# ATmega328p-DHT11-DS1307-LCD.net
KiCad netlist of a schematic drawn in EAGLE
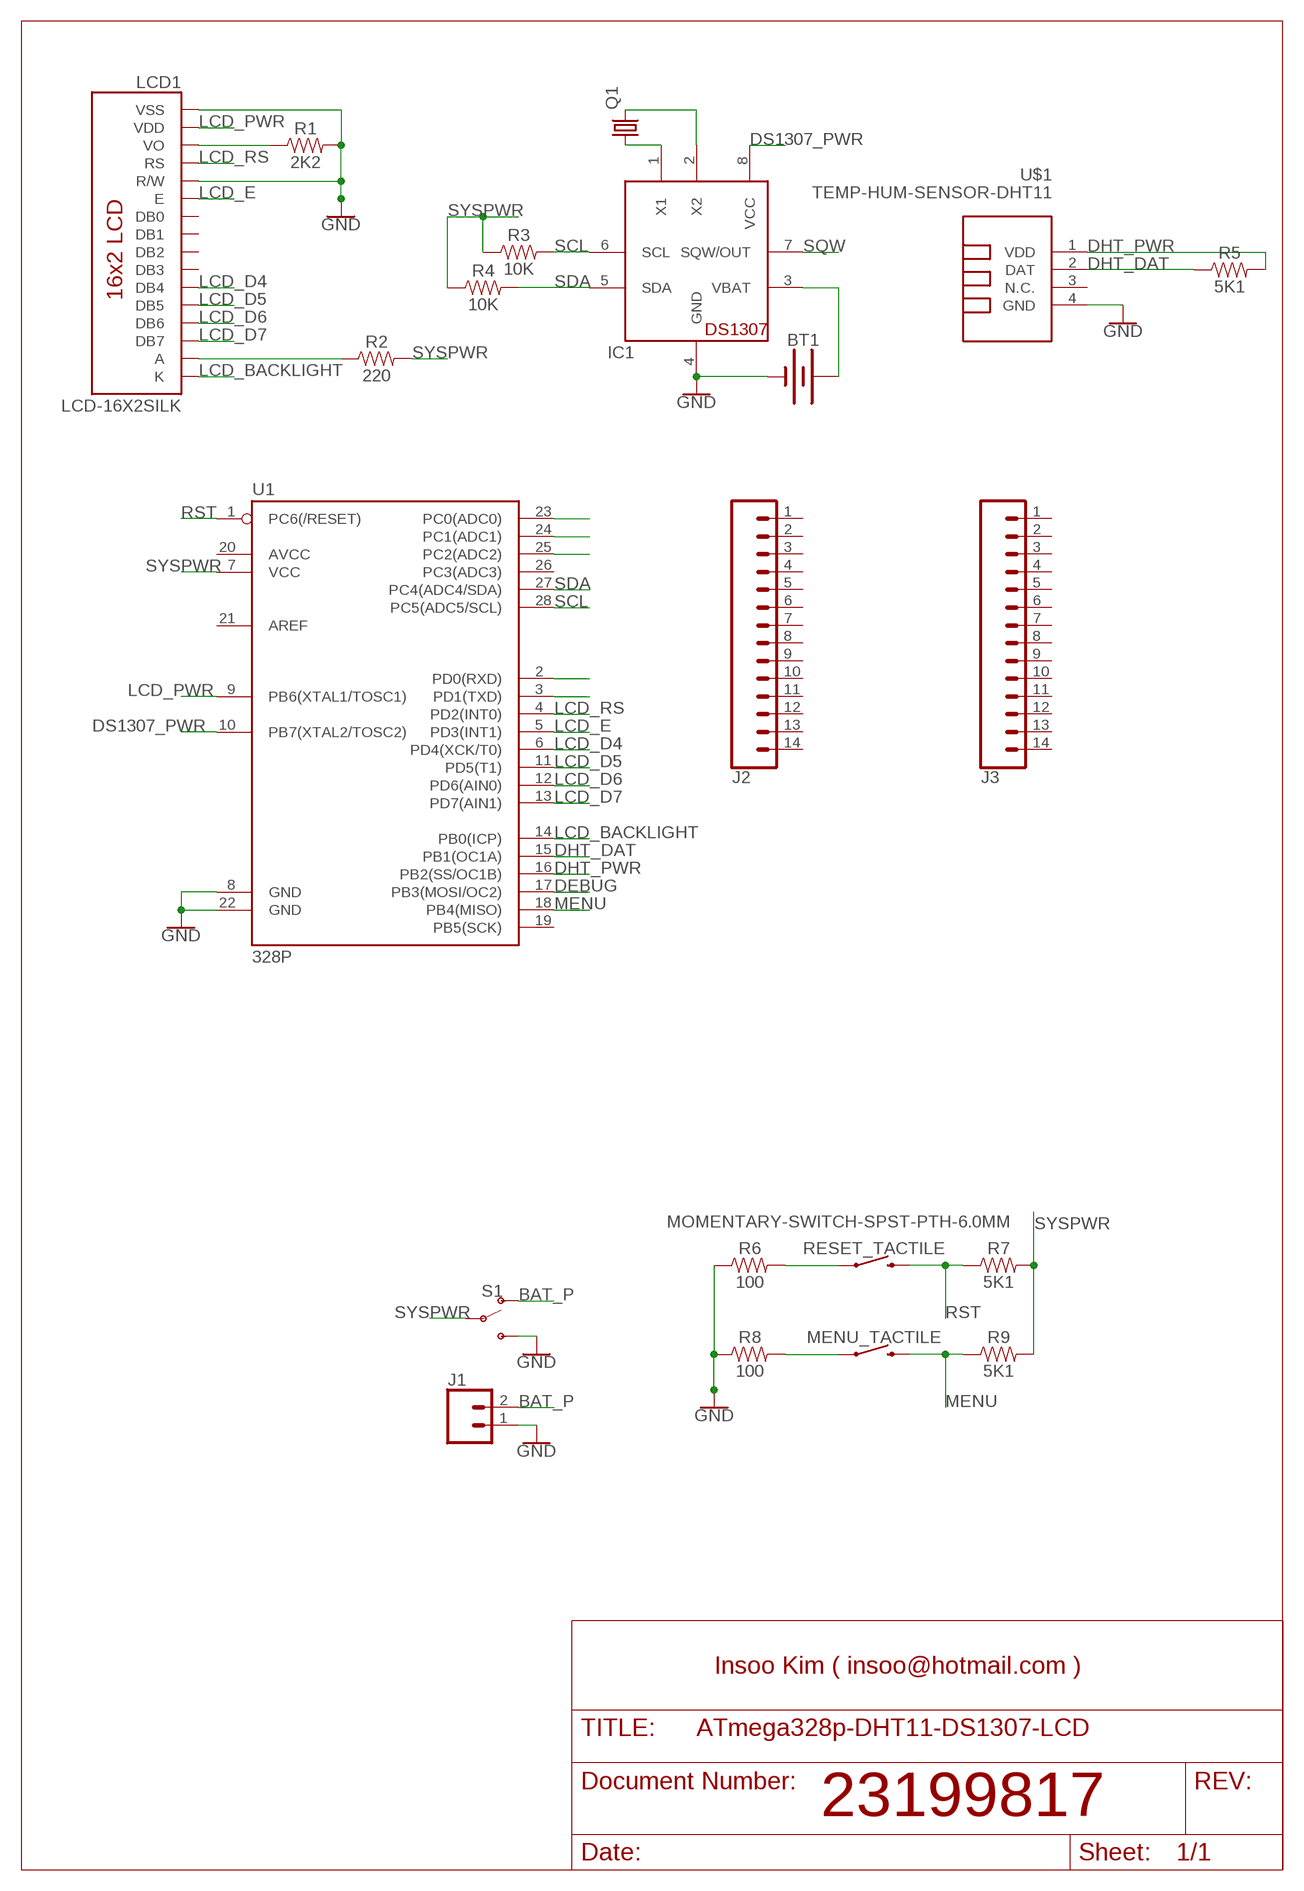
[diagram p0: schematic, sheet 1]

(export (version "E")
  (design (tool "Eeschema 10.0.6"))
  (components
    (comp (ref "BT1")
      (value "BATTERY-20MM_PTH")
      (footprint "eagle-import:BATTCOM_20MM_PTH")
      (libsource (lib "eagle-import") (part "BATTERY-20MM_PTH"))
    )
    (comp (ref "IC1")
      (value "DS1307")
      (footprint "eagle-import:DIL08")
      (libsource (lib "eagle-import") (part "DS1307"))
    )
    (comp (ref "J1")
      (value "CONN_02")
      (footprint "eagle-import:1X02")
      (libsource (lib "eagle-import") (part "CONN_02"))
    )
    (comp (ref "J2")
      (value "CONN_14")
      (footprint "eagle-import:1X14")
      (libsource (lib "eagle-import") (part "CONN_14"))
    )
    (comp (ref "J3")
      (value "CONN_14")
      (footprint "eagle-import:1X14")
      (libsource (lib "eagle-import") (part "CONN_14"))
    )
    (comp (ref "LCD1")
      (value "LCD-16X2SILK")
      (footprint "eagle-import:LCD-16X2")
      (libsource (lib "eagle-import") (part "LCD-16X2SILK"))
    )
    (comp (ref "MENU_TACTILE")
      (value "MOMENTARY-SWITCH-SPST-PTH-6.0MM")
      (footprint "eagle-import:TACTILE_SWITCH_PTH_6.0MM")
      (libsource (lib "eagle-import") (part "MOMENTARY-SWITCH-SPST-PTH-6.0MM"))
    )
    (comp (ref "Q1")
      (value "CRYSTALTC26H")
      (footprint "eagle-import:TC26H")
      (libsource (lib "eagle-import") (part "CRYSTALTC26H"))
    )
    (comp (ref "R1")
      (value "2K2")
      (footprint "eagle-import:AXIAL-0.3")
      (libsource (lib "eagle-import") (part "1KOHM-HORIZ-1/4W-5%"))
    )
    (comp (ref "R2")
      (value "220")
      (footprint "eagle-import:AXIAL-0.3")
      (libsource (lib "eagle-import") (part "1KOHM-HORIZ-1/4W-5%"))
    )
    (comp (ref "R3")
      (value "10K")
      (footprint "eagle-import:AXIAL-0.3")
      (libsource (lib "eagle-import") (part "1KOHM-HORIZ-1/4W-5%"))
    )
    (comp (ref "R4")
      (value "10K")
      (footprint "eagle-import:AXIAL-0.3")
      (libsource (lib "eagle-import") (part "1KOHM-HORIZ-1/4W-5%"))
    )
    (comp (ref "R5")
      (value "5K1")
      (footprint "eagle-import:AXIAL-0.3")
      (libsource (lib "eagle-import") (part "1KOHM-HORIZ-1/4W-5%"))
    )
    (comp (ref "R6")
      (value "100")
      (footprint "eagle-import:AXIAL-0.3")
      (libsource (lib "eagle-import") (part "1KOHM-HORIZ-1/4W-5%"))
    )
    (comp (ref "R7")
      (value "5K1")
      (footprint "eagle-import:AXIAL-0.3")
      (libsource (lib "eagle-import") (part "1KOHM-HORIZ-1/4W-5%"))
    )
    (comp (ref "R8")
      (value "100")
      (footprint "eagle-import:AXIAL-0.3")
      (libsource (lib "eagle-import") (part "1KOHM-HORIZ-1/4W-5%"))
    )
    (comp (ref "R9")
      (value "5K1")
      (footprint "eagle-import:AXIAL-0.3")
      (libsource (lib "eagle-import") (part "1KOHM-HORIZ-1/4W-5%"))
    )
    (comp (ref "RESET_TACTILE")
      (value "MOMENTARY-SWITCH-SPST-PTH-6.0MM")
      (footprint "eagle-import:TACTILE_SWITCH_PTH_6.0MM")
      (libsource (lib "eagle-import") (part "MOMENTARY-SWITCH-SPST-PTH-6.0MM"))
    )
    (comp (ref "S1")
      (value "SWITCH-SPDT-PTH-11.6X4.0MM")
      (footprint "eagle-import:SWITCH_SPDT_PTH_11.6X4.0MM")
      (libsource (lib "eagle-import") (part "SWITCH-SPDT-PTH-11.6X4.0MM"))
    )
    (comp (ref "U$1")
      (value "TEMP-HUM-SENSOR-DHT11")
      (footprint "eagle-import:TEMP-HUM-SENSOR-DHT11")
      (libsource (lib "eagle-import") (part "TEMP-HUM-SENSOR-DHT11"))
    )
    (comp (ref "U1")
      (value "328P")
      (footprint "eagle-import:DIP28")
      (libsource (lib "eagle-import") (part "ATMEGA328P_PDIP"))
    )
  )
  (nets
    (net (code "1") (name "/BAT_P") (class "Default")
      (node (ref "J1") (pin "2") (pinfunction "2_2") (pintype "passive"))
      (node (ref "S1") (pin "1") (pinfunction "O_1") (pintype "passive"))
    )
    (net (code "2") (name "/DEBUG") (class "Default")
      (node (ref "U1") (pin "17") (pinfunction "PB3(MOSI/OC2)_17") (pintype "bidirectional"))
    )
    (net (code "3") (name "/DHT_DAT") (class "Default")
      (node (ref "R5") (pin "P$1") (pinfunction "1_P$1") (pintype "passive"))
      (node (ref "U$1") (pin "2") (pinfunction "DAT_2") (pintype "bidirectional"))
      (node (ref "U1") (pin "15") (pinfunction "PB1(OC1A)_15") (pintype "bidirectional"))
    )
    (net (code "4") (name "/DHT_PWR") (class "Default")
      (node (ref "R5") (pin "P$2") (pinfunction "2_P$2") (pintype "passive"))
      (node (ref "U$1") (pin "1") (pinfunction "VDD_1") (pintype "power_in"))
      (node (ref "U1") (pin "16") (pinfunction "PB2(SS/OC1B)_16") (pintype "bidirectional"))
    )
    (net (code "5") (name "/DS1307_PWR") (class "Default")
      (node (ref "IC1") (pin "8") (pinfunction "VCC_8") (pintype "power_in"))
      (node (ref "U1") (pin "10") (pinfunction "PB7(XTAL2/TOSC2)_10") (pintype "bidirectional"))
    )
    (net (code "6") (name "/LCD_BACKLIGHT") (class "Default")
      (node (ref "LCD1") (pin "16") (pinfunction "K_16") (pintype "power_in"))
      (node (ref "U1") (pin "14") (pinfunction "PB0(ICP)_14") (pintype "bidirectional"))
    )
    (net (code "7") (name "/LCD_D4") (class "Default")
      (node (ref "LCD1") (pin "11") (pinfunction "DB4_11") (pintype "bidirectional"))
      (node (ref "U1") (pin "6") (pinfunction "PD4(XCK/T0)_6") (pintype "bidirectional"))
    )
    (net (code "8") (name "/LCD_D5") (class "Default")
      (node (ref "LCD1") (pin "12") (pinfunction "DB5_12") (pintype "bidirectional"))
      (node (ref "U1") (pin "11") (pinfunction "PD5(T1)_11") (pintype "bidirectional"))
    )
    (net (code "9") (name "/LCD_D6") (class "Default")
      (node (ref "LCD1") (pin "13") (pinfunction "DB6_13") (pintype "bidirectional"))
      (node (ref "U1") (pin "12") (pinfunction "PD6(AIN0)_12") (pintype "bidirectional"))
    )
    (net (code "10") (name "/LCD_D7") (class "Default")
      (node (ref "LCD1") (pin "14") (pinfunction "DB7_14") (pintype "bidirectional"))
      (node (ref "U1") (pin "13") (pinfunction "PD7(AIN1)_13") (pintype "bidirectional"))
    )
    (net (code "11") (name "/LCD_E") (class "Default")
      (node (ref "LCD1") (pin "6") (pinfunction "E_6") (pintype "input"))
      (node (ref "U1") (pin "5") (pinfunction "PD3(INT1)_5") (pintype "bidirectional"))
    )
    (net (code "12") (name "/LCD_PWR") (class "Default")
      (node (ref "LCD1") (pin "2") (pinfunction "VDD_2") (pintype "power_in"))
      (node (ref "U1") (pin "9") (pinfunction "PB6(XTAL1/TOSC1)_9") (pintype "bidirectional"))
    )
    (net (code "13") (name "/LCD_RS") (class "Default")
      (node (ref "LCD1") (pin "4") (pinfunction "RS_4") (pintype "input"))
      (node (ref "U1") (pin "4") (pinfunction "PD2(INT0)_4") (pintype "bidirectional"))
    )
    (net (code "14") (name "/MENU") (class "Default")
      (node (ref "MENU_TACTILE") (pin "3") (pinfunction "2_3") (pintype "passive"))
      (node (ref "R9") (pin "P$1") (pinfunction "1_P$1") (pintype "passive"))
      (node (ref "U1") (pin "18") (pinfunction "PB4(MISO)_18") (pintype "bidirectional"))
    )
    (net (code "15") (name "/RST") (class "Default")
      (node (ref "R7") (pin "P$1") (pinfunction "1_P$1") (pintype "passive"))
      (node (ref "RESET_TACTILE") (pin "3") (pinfunction "2_3") (pintype "passive"))
      (node (ref "U1") (pin "1") (pinfunction "PC6(/RESET)_1") (pintype "bidirectional"))
    )
    (net (code "16") (name "/SCL") (class "Default")
      (node (ref "IC1") (pin "6") (pinfunction "SCL_6") (pintype "bidirectional"))
      (node (ref "R3") (pin "P$2") (pinfunction "2_P$2") (pintype "passive"))
      (node (ref "U1") (pin "28") (pinfunction "PC5(ADC5/SCL)_28") (pintype "bidirectional"))
    )
    (net (code "17") (name "/SDA") (class "Default")
      (node (ref "IC1") (pin "5") (pinfunction "SDA_5") (pintype "bidirectional"))
      (node (ref "R4") (pin "P$2") (pinfunction "2_P$2") (pintype "passive"))
      (node (ref "U1") (pin "27") (pinfunction "PC4(ADC4/SDA)_27") (pintype "bidirectional"))
    )
    (net (code "18") (name "/SQW") (class "Default")
      (node (ref "IC1") (pin "7") (pinfunction "SQW/OUT_7") (pintype "bidirectional"))
    )
    (net (code "19") (name "/SYSPWR") (class "Default")
      (node (ref "R2") (pin "P$2") (pinfunction "2_P$2") (pintype "passive"))
      (node (ref "R3") (pin "P$1") (pinfunction "1_P$1") (pintype "passive"))
      (node (ref "R4") (pin "P$1") (pinfunction "1_P$1") (pintype "passive"))
      (node (ref "R7") (pin "P$2") (pinfunction "2_P$2") (pintype "passive"))
      (node (ref "R9") (pin "P$2") (pinfunction "2_P$2") (pintype "passive"))
      (node (ref "S1") (pin "2") (pinfunction "P_2") (pintype "passive"))
      (node (ref "U1") (pin "7") (pinfunction "VCC_7") (pintype "bidirectional"))
    )
    (net (code "20") (name "GND") (class "Default")
      (node (ref "BT1") (pin "2") (pinfunction "-_2") (pintype "power_in"))
      (node (ref "IC1") (pin "4") (pinfunction "GND_4") (pintype "power_in"))
      (node (ref "J1") (pin "1") (pinfunction "1_1") (pintype "passive"))
      (node (ref "LCD1") (pin "1") (pinfunction "VSS_1") (pintype "power_in"))
      (node (ref "LCD1") (pin "5") (pinfunction "R/W_5") (pintype "input"))
      (node (ref "R1") (pin "P$2") (pinfunction "2_P$2") (pintype "passive"))
      (node (ref "R6") (pin "P$1") (pinfunction "1_P$1") (pintype "passive"))
      (node (ref "R8") (pin "P$1") (pinfunction "1_P$1") (pintype "passive"))
      (node (ref "S1") (pin "3") (pinfunction "S_3") (pintype "passive"))
      (node (ref "U$1") (pin "4") (pinfunction "GND_4") (pintype "power_in"))
      (node (ref "U1") (pin "22") (pinfunction "GND_22") (pintype "bidirectional"))
      (node (ref "U1") (pin "8") (pinfunction "GND_8") (pintype "bidirectional"))
    )
    (net (code "21") (name "Net-(BT1-+)") (class "Default")
      (node (ref "BT1") (pin "1") (pinfunction "+_1") (pintype "power_in"))
      (node (ref "IC1") (pin "3") (pinfunction "VBAT_3") (pintype "power_in"))
    )
    (net (code "22") (name "Net-(IC1-X1)") (class "Default")
      (node (ref "IC1") (pin "1") (pinfunction "X1_1") (pintype "passive"))
      (node (ref "Q1") (pin "1") (pinfunction "1_1") (pintype "passive"))
    )
    (net (code "23") (name "Net-(IC1-X2)") (class "Default")
      (node (ref "IC1") (pin "2") (pinfunction "X2_2") (pintype "passive"))
      (node (ref "Q1") (pin "2") (pinfunction "2_2") (pintype "passive"))
    )
    (net (code "24") (name "Net-(LCD1-A)") (class "Default")
      (node (ref "LCD1") (pin "15") (pinfunction "A_15") (pintype "power_in"))
      (node (ref "R2") (pin "P$1") (pinfunction "1_P$1") (pintype "passive"))
    )
    (net (code "25") (name "Net-(LCD1-VO)") (class "Default")
      (node (ref "LCD1") (pin "3") (pinfunction "VO_3") (pintype "bidirectional"))
      (node (ref "R1") (pin "P$1") (pinfunction "1_P$1") (pintype "passive"))
    )
    (net (code "26") (name "Net-(R6-2)") (class "Default")
      (node (ref "R6") (pin "P$2") (pinfunction "2_P$2") (pintype "passive"))
      (node (ref "RESET_TACTILE") (pin "1") (pinfunction "1_1") (pintype "passive"))
    )
    (net (code "27") (name "Net-(R8-2)") (class "Default")
      (node (ref "MENU_TACTILE") (pin "1") (pinfunction "1_1") (pintype "passive"))
      (node (ref "R8") (pin "P$2") (pinfunction "2_P$2") (pintype "passive"))
    )
    (net (code "28") (name "unconnected-(J2-Pad1)") (class "Default")
      (node (ref "J2") (pin "1") (pinfunction "1_1") (pintype "passive"))
    )
    (net (code "29") (name "unconnected-(J2-Pad2)") (class "Default")
      (node (ref "J2") (pin "2") (pinfunction "2_2") (pintype "passive"))
    )
    (net (code "30") (name "unconnected-(J2-Pad3)") (class "Default")
      (node (ref "J2") (pin "3") (pinfunction "3_3") (pintype "passive"))
    )
    (net (code "31") (name "unconnected-(J2-Pad4)") (class "Default")
      (node (ref "J2") (pin "4") (pinfunction "4_4") (pintype "passive"))
    )
    (net (code "32") (name "unconnected-(J2-Pad5)") (class "Default")
      (node (ref "J2") (pin "5") (pinfunction "5_5") (pintype "passive"))
    )
    (net (code "33") (name "unconnected-(J2-Pad6)") (class "Default")
      (node (ref "J2") (pin "6") (pinfunction "6_6") (pintype "passive"))
    )
    (net (code "34") (name "unconnected-(J2-Pad7)") (class "Default")
      (node (ref "J2") (pin "7") (pinfunction "7_7") (pintype "passive"))
    )
    (net (code "35") (name "unconnected-(J2-Pad8)") (class "Default")
      (node (ref "J2") (pin "8") (pinfunction "8_8") (pintype "passive"))
    )
    (net (code "36") (name "unconnected-(J2-Pad9)") (class "Default")
      (node (ref "J2") (pin "9") (pinfunction "9_9") (pintype "passive"))
    )
    (net (code "37") (name "unconnected-(J2-Pad10)") (class "Default")
      (node (ref "J2") (pin "10") (pinfunction "10_10") (pintype "passive"))
    )
    (net (code "38") (name "unconnected-(J2-Pad11)") (class "Default")
      (node (ref "J2") (pin "11") (pinfunction "11_11") (pintype "passive"))
    )
    (net (code "39") (name "unconnected-(J2-Pad12)") (class "Default")
      (node (ref "J2") (pin "12") (pinfunction "12_12") (pintype "passive"))
    )
    (net (code "40") (name "unconnected-(J2-Pad13)") (class "Default")
      (node (ref "J2") (pin "13") (pinfunction "13_13") (pintype "passive"))
    )
    (net (code "41") (name "unconnected-(J2-Pad14)") (class "Default")
      (node (ref "J2") (pin "14") (pinfunction "14_14") (pintype "passive"))
    )
    (net (code "42") (name "unconnected-(J3-Pad1)") (class "Default")
      (node (ref "J3") (pin "1") (pinfunction "1_1") (pintype "passive"))
    )
    (net (code "43") (name "unconnected-(J3-Pad2)") (class "Default")
      (node (ref "J3") (pin "2") (pinfunction "2_2") (pintype "passive"))
    )
    (net (code "44") (name "unconnected-(J3-Pad3)") (class "Default")
      (node (ref "J3") (pin "3") (pinfunction "3_3") (pintype "passive"))
    )
    (net (code "45") (name "unconnected-(J3-Pad4)") (class "Default")
      (node (ref "J3") (pin "4") (pinfunction "4_4") (pintype "passive"))
    )
    (net (code "46") (name "unconnected-(J3-Pad5)") (class "Default")
      (node (ref "J3") (pin "5") (pinfunction "5_5") (pintype "passive"))
    )
    (net (code "47") (name "unconnected-(J3-Pad6)") (class "Default")
      (node (ref "J3") (pin "6") (pinfunction "6_6") (pintype "passive"))
    )
    (net (code "48") (name "unconnected-(J3-Pad7)") (class "Default")
      (node (ref "J3") (pin "7") (pinfunction "7_7") (pintype "passive"))
    )
    (net (code "49") (name "unconnected-(J3-Pad8)") (class "Default")
      (node (ref "J3") (pin "8") (pinfunction "8_8") (pintype "passive"))
    )
    (net (code "50") (name "unconnected-(J3-Pad9)") (class "Default")
      (node (ref "J3") (pin "9") (pinfunction "9_9") (pintype "passive"))
    )
    (net (code "51") (name "unconnected-(J3-Pad10)") (class "Default")
      (node (ref "J3") (pin "10") (pinfunction "10_10") (pintype "passive"))
    )
    (net (code "52") (name "unconnected-(J3-Pad11)") (class "Default")
      (node (ref "J3") (pin "11") (pinfunction "11_11") (pintype "passive"))
    )
    (net (code "53") (name "unconnected-(J3-Pad12)") (class "Default")
      (node (ref "J3") (pin "12") (pinfunction "12_12") (pintype "passive"))
    )
    (net (code "54") (name "unconnected-(J3-Pad13)") (class "Default")
      (node (ref "J3") (pin "13") (pinfunction "13_13") (pintype "passive"))
    )
    (net (code "55") (name "unconnected-(J3-Pad14)") (class "Default")
      (node (ref "J3") (pin "14") (pinfunction "14_14") (pintype "passive"))
    )
    (net (code "56") (name "unconnected-(LCD1-DB0-Pad7)") (class "Default")
      (node (ref "LCD1") (pin "7") (pinfunction "DB0_7") (pintype "bidirectional"))
    )
    (net (code "57") (name "unconnected-(LCD1-DB1-Pad8)") (class "Default")
      (node (ref "LCD1") (pin "8") (pinfunction "DB1_8") (pintype "bidirectional"))
    )
    (net (code "58") (name "unconnected-(LCD1-DB2-Pad9)") (class "Default")
      (node (ref "LCD1") (pin "9") (pinfunction "DB2_9") (pintype "bidirectional"))
    )
    (net (code "59") (name "unconnected-(LCD1-DB3-Pad10)") (class "Default")
      (node (ref "LCD1") (pin "10") (pinfunction "DB3_10") (pintype "bidirectional"))
    )
    (net (code "60") (name "unconnected-(U$1-N.C.-Pad3)") (class "Default")
      (node (ref "U$1") (pin "3") (pinfunction "N.C._3") (pintype "passive"))
    )
    (net (code "61") (name "unconnected-(U1-AREF-Pad21)") (class "Default")
      (node (ref "U1") (pin "21") (pinfunction "AREF_21") (pintype "bidirectional"))
    )
    (net (code "62") (name "unconnected-(U1-AVCC-Pad20)") (class "Default")
      (node (ref "U1") (pin "20") (pinfunction "AVCC_20") (pintype "bidirectional"))
    )
    (net (code "63") (name "unconnected-(U1-PB5(SCK)-Pad19)") (class "Default")
      (node (ref "U1") (pin "19") (pinfunction "PB5(SCK)_19") (pintype "bidirectional"))
    )
    (net (code "64") (name "unconnected-(U1-PC0(ADC0)-Pad23)") (class "Default")
      (node (ref "U1") (pin "23") (pinfunction "PC0(ADC0)_23") (pintype "bidirectional"))
    )
    (net (code "65") (name "unconnected-(U1-PC1(ADC1)-Pad24)") (class "Default")
      (node (ref "U1") (pin "24") (pinfunction "PC1(ADC1)_24") (pintype "bidirectional"))
    )
    (net (code "66") (name "unconnected-(U1-PC2(ADC2)-Pad25)") (class "Default")
      (node (ref "U1") (pin "25") (pinfunction "PC2(ADC2)_25") (pintype "bidirectional"))
    )
    (net (code "67") (name "unconnected-(U1-PC3(ADC3)-Pad26)") (class "Default")
      (node (ref "U1") (pin "26") (pinfunction "PC3(ADC3)_26") (pintype "bidirectional"))
    )
    (net (code "68") (name "unconnected-(U1-PD0(RXD)-Pad2)") (class "Default")
      (node (ref "U1") (pin "2") (pinfunction "PD0(RXD)_2") (pintype "bidirectional"))
    )
    (net (code "69") (name "unconnected-(U1-PD1(TXD)-Pad3)") (class "Default")
      (node (ref "U1") (pin "3") (pinfunction "PD1(TXD)_3") (pintype "bidirectional"))
    )
  )
)
